# CPU.net
KiCad netlist of a schematic drawn in Altium Designer
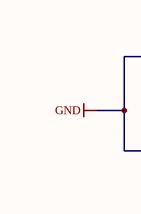
[diagram p0: CPU.SchDoc, top left]
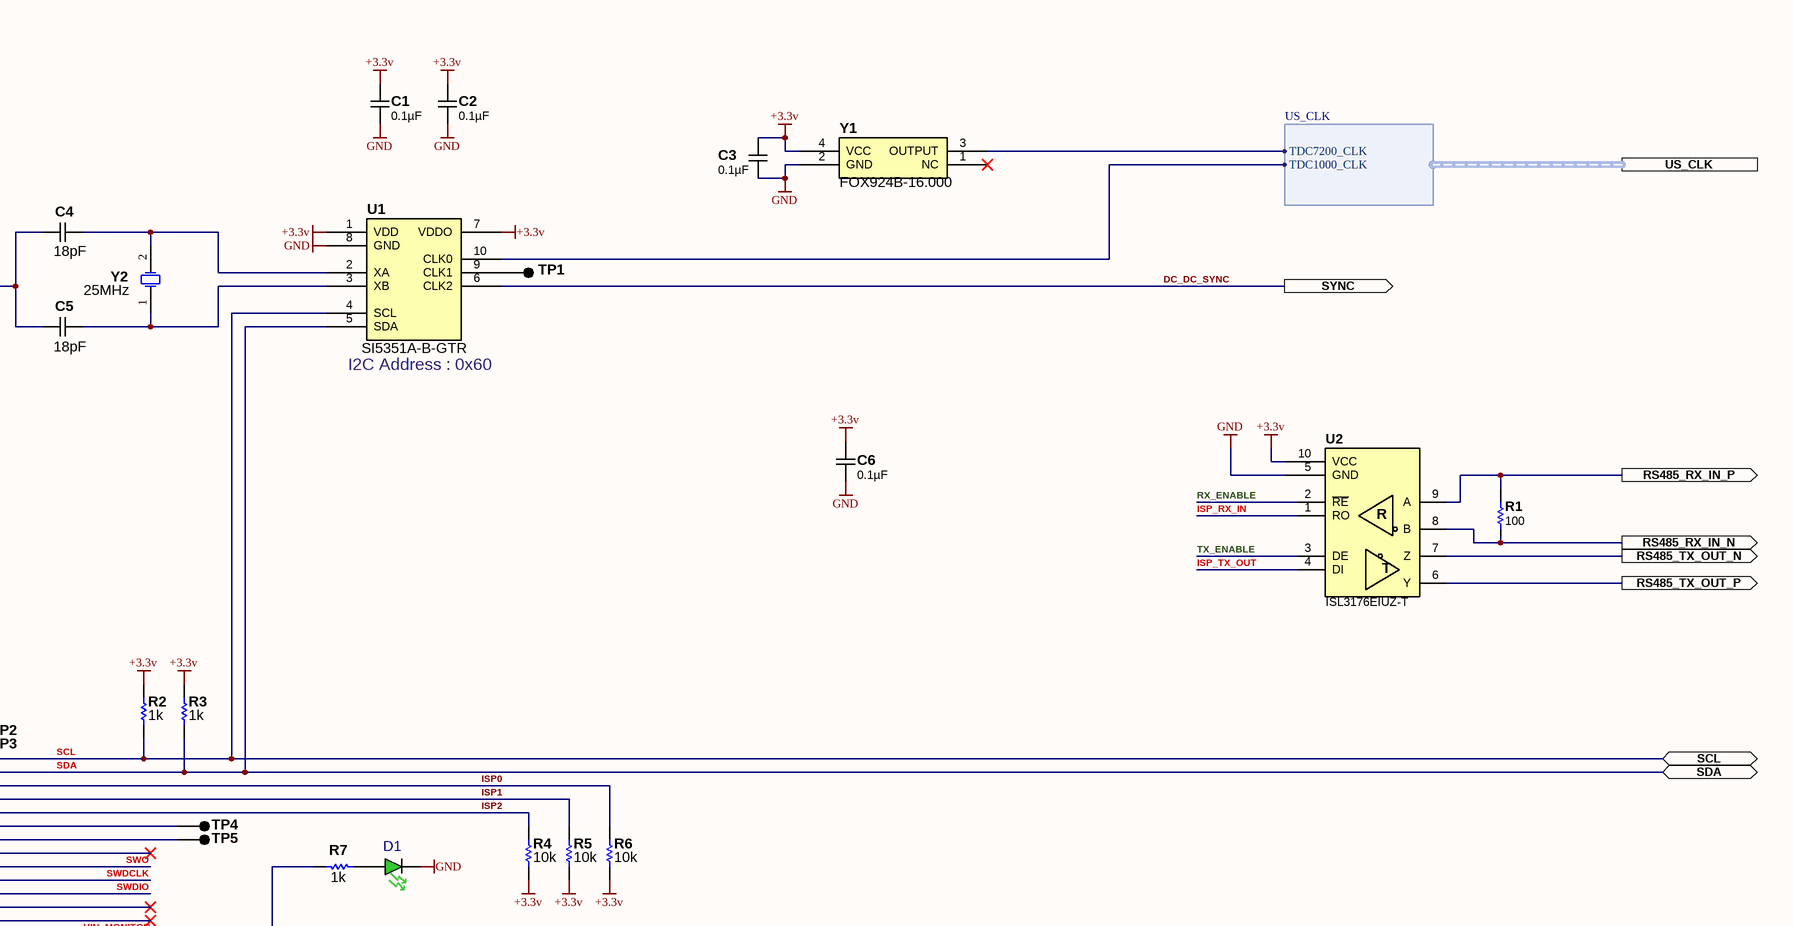
[diagram p1: CPU.SchDoc, top right]
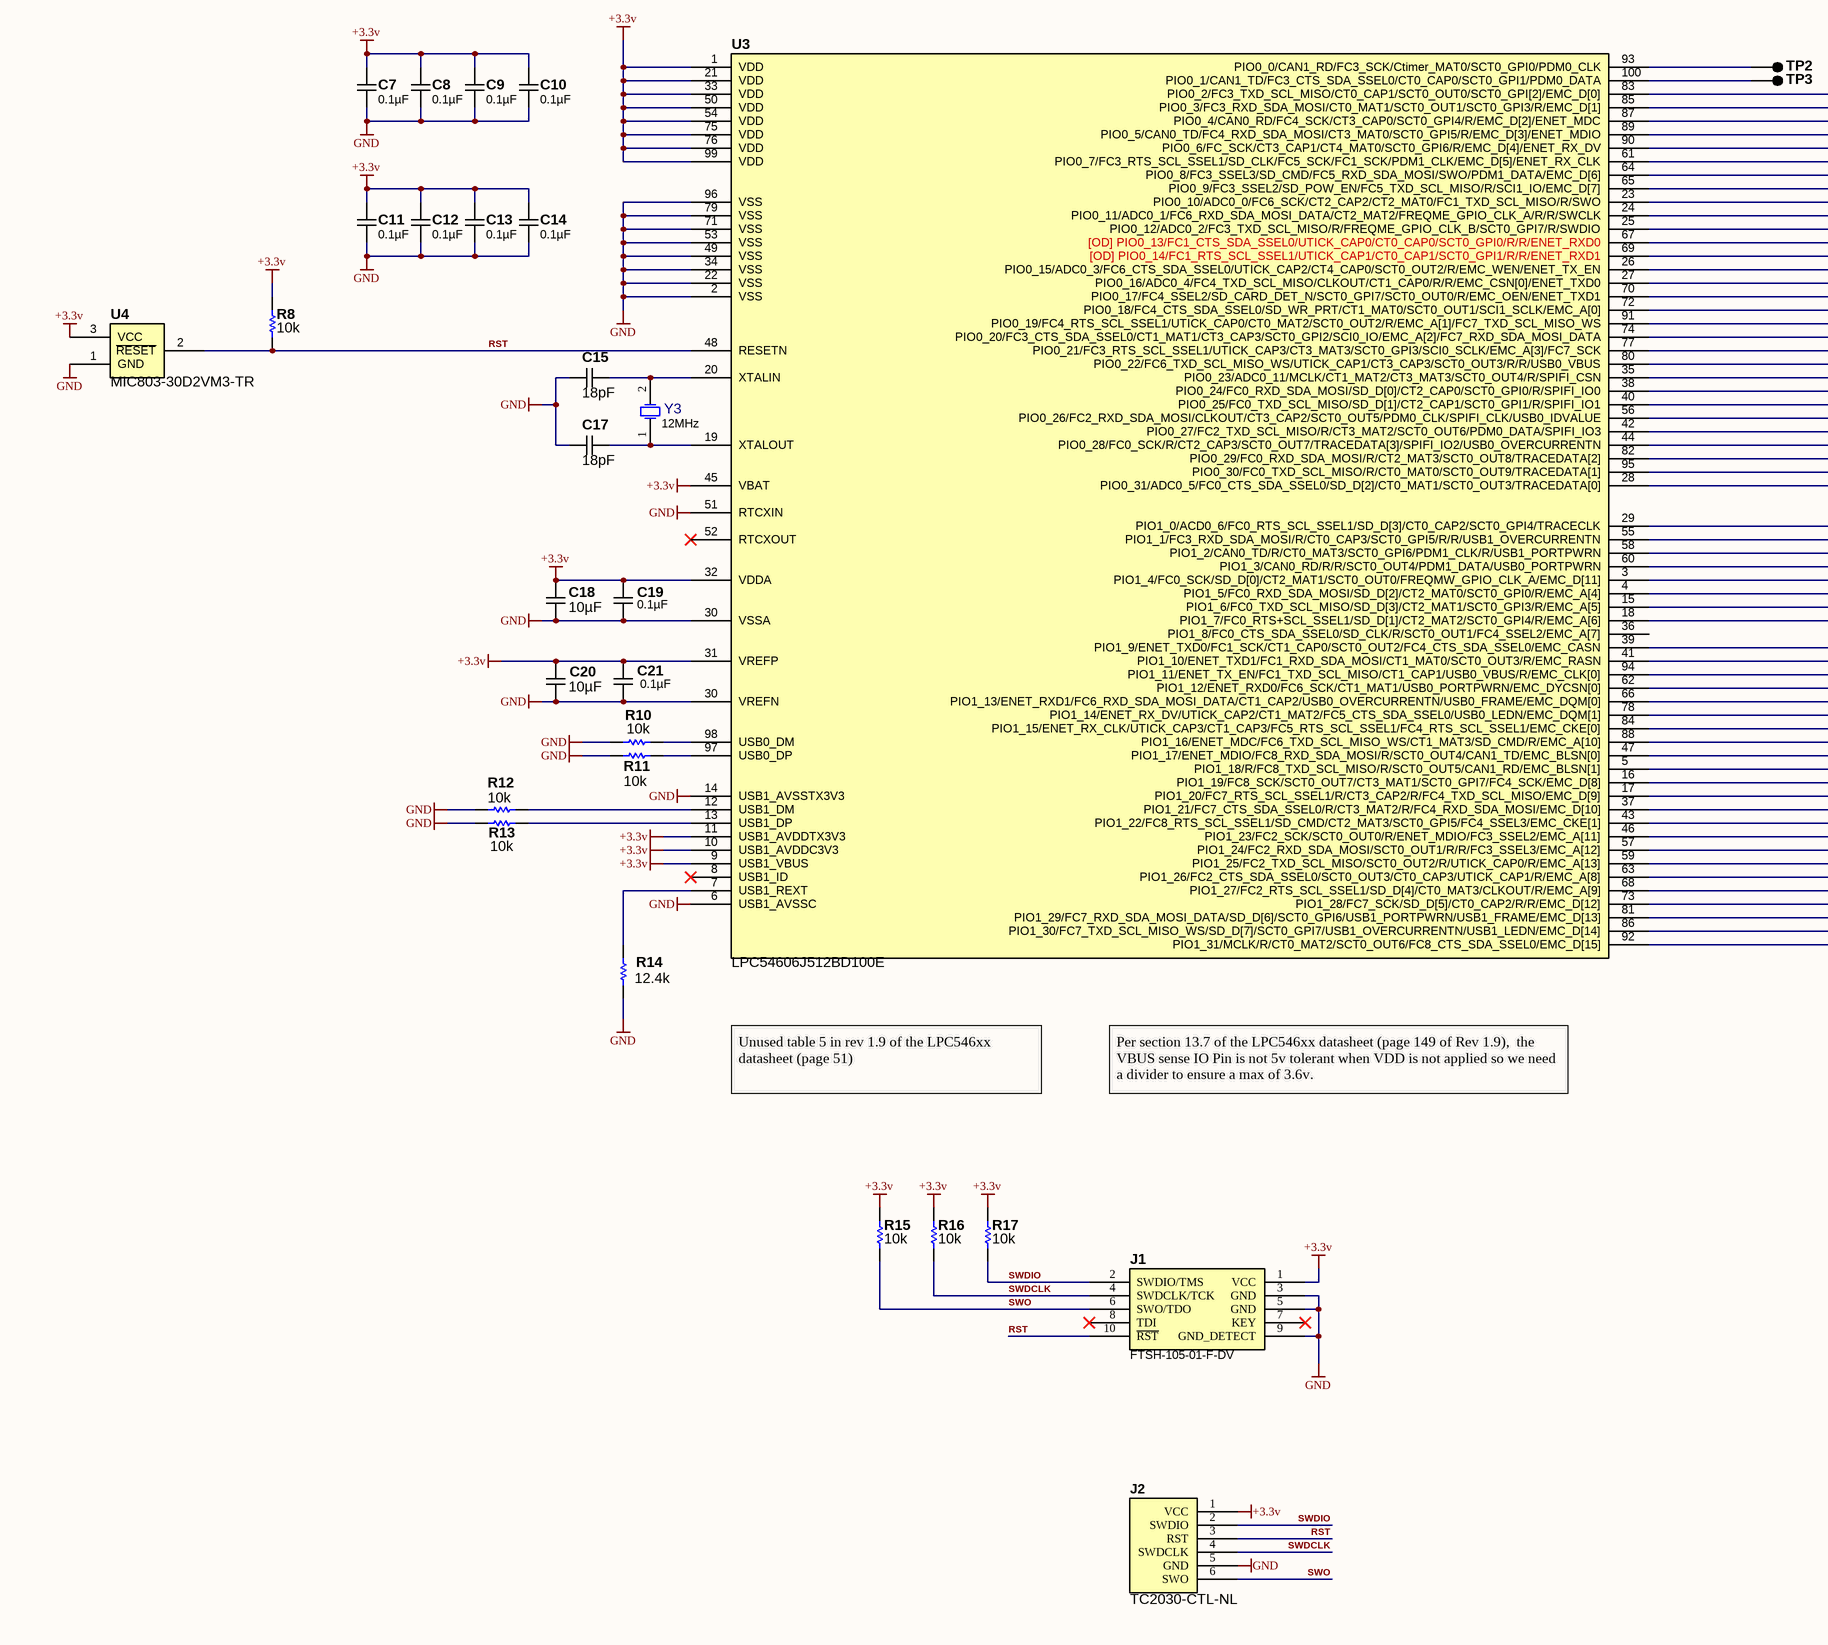
[diagram p2: CPU.SchDoc, bottom left]
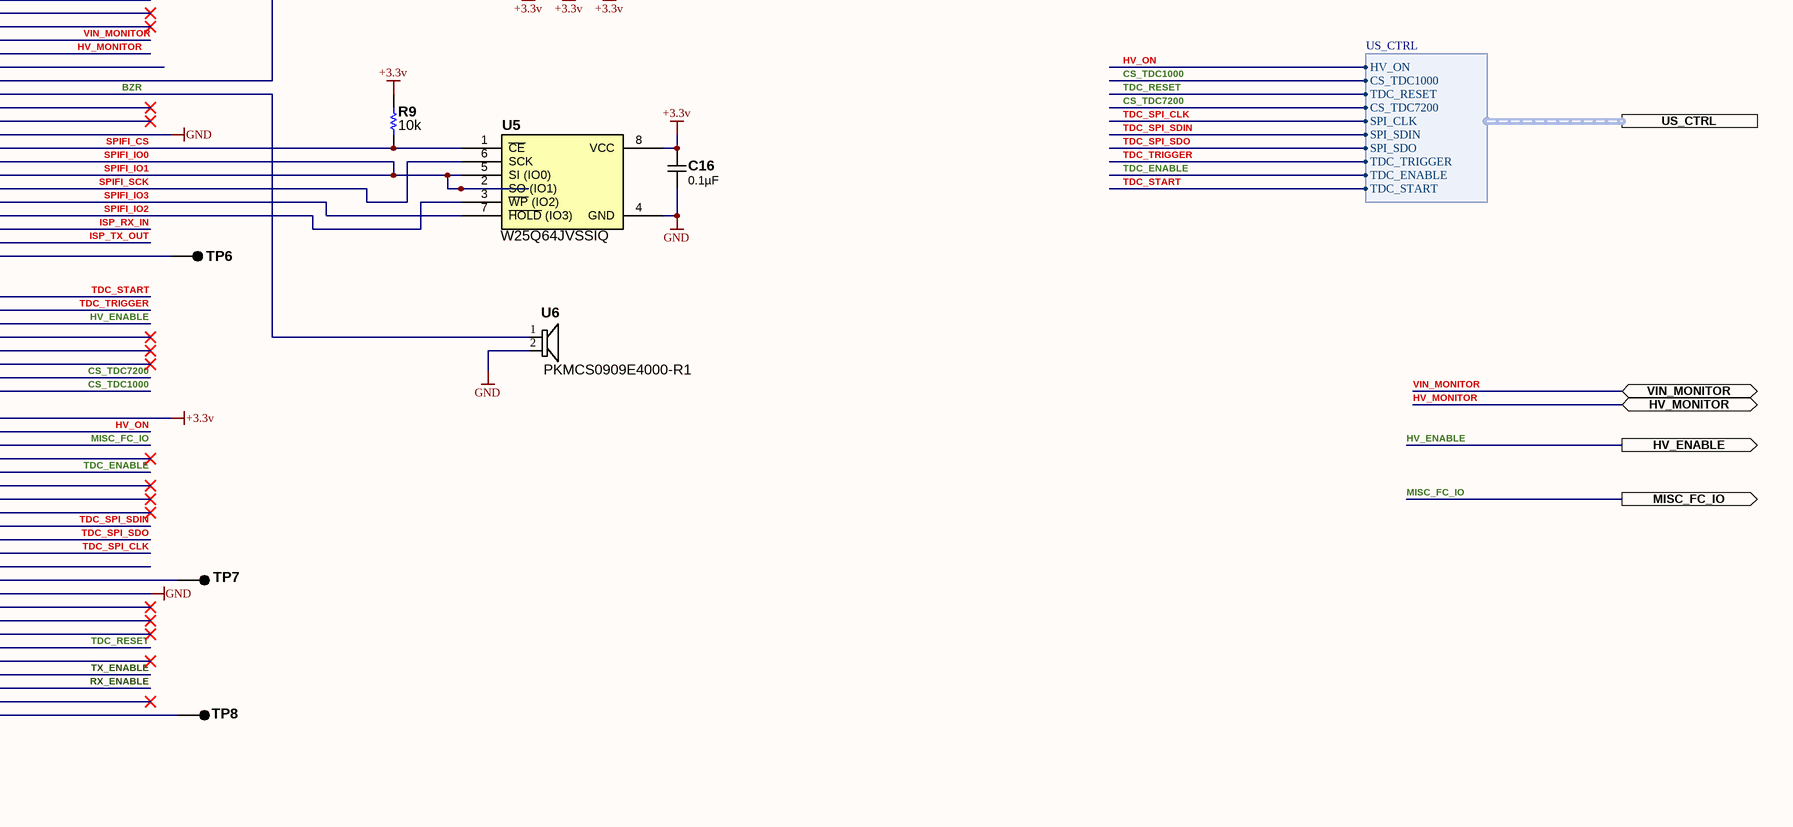
[diagram p3: CPU.SchDoc, bottom right]

(export (version "E")
  (design (tool "Eeschema 10.0.6"))
  (components
    (comp (ref "C1")
      (value "0.1µF")
      (footprint "C0603_0.90MM_HD")
      (description "CAP CER 0.1UF 50V X7R 0603")
      (fields
        (field (name "MANUFACTURER PART NUMBER") "CGA3E2X7R1H104K080AE")
        (field (name "MANUFACTURER") "TDK Corporation")
      )
      (libsource (lib "Capacitors - TDK- AEC-Q200") (part "C_2P_NP"))
    )
    (comp (ref "C2")
      (value "0.1µF")
      (footprint "C0603_0.90MM_HD")
      (description "CAP CER 0.1UF 50V X7R 0603")
      (fields
        (field (name "MANUFACTURER PART NUMBER") "CGA3E2X7R1H104K080AE")
        (field (name "MANUFACTURER") "TDK Corporation")
      )
      (libsource (lib "Capacitors - TDK- AEC-Q200") (part "C_2P_NP"))
    )
    (comp (ref "C3")
      (value "0.1µF")
      (footprint "C0603_0.90MM_HD")
      (description "CAP CER 0.1UF 50V X7R 0603")
      (fields
        (field (name "MANUFACTURER PART NUMBER") "CGA3E2X7R1H104K080AE")
        (field (name "MANUFACTURER") "TDK Corporation")
      )
      (libsource (lib "Capacitors - TDK- AEC-Q200") (part "C_2P_NP"))
    )
    (comp (ref "C4")
      (value "18pF")
      (footprint "C0603_0.90MM_HD")
      (description "CAP CER 18PF 50V C0G 0603")
      (fields
        (field (name "MANUFACTURER PART NUMBER") "CGA3E2C0G1H180J080AA")
        (field (name "MANUFACTURER") "TDK Corporation")
      )
      (libsource (lib "Capacitors - TDK- AEC-Q200") (part "C_2P_NP"))
    )
    (comp (ref "C5")
      (value "18pF")
      (footprint "C0603_0.90MM_HD")
      (description "CAP CER 18PF 50V C0G 0603")
      (fields
        (field (name "MANUFACTURER PART NUMBER") "CGA3E2C0G1H180J080AA")
        (field (name "MANUFACTURER") "TDK Corporation")
      )
      (libsource (lib "Capacitors - TDK- AEC-Q200") (part "C_2P_NP"))
    )
    (comp (ref "C6")
      (value "0.1µF")
      (footprint "C0603_0.90MM_HD")
      (description "CAP CER 0.1UF 50V X7R 0603")
      (fields
        (field (name "MANUFACTURER PART NUMBER") "CGA3E2X7R1H104K080AE")
        (field (name "MANUFACTURER") "TDK Corporation")
      )
      (libsource (lib "Capacitors - TDK- AEC-Q200") (part "C_2P_NP"))
    )
    (comp (ref "C7")
      (value "0.1µF")
      (footprint "C0603_0.90MM_HD")
      (description "CAP CER 0.1UF 50V X7R 0603")
      (fields
        (field (name "MANUFACTURER PART NUMBER") "CGA3E2X7R1H104K080AE")
        (field (name "MANUFACTURER") "TDK Corporation")
      )
      (libsource (lib "Capacitors - TDK- AEC-Q200") (part "C_2P_NP"))
    )
    (comp (ref "C8")
      (value "0.1µF")
      (footprint "C0603_0.90MM_HD")
      (description "CAP CER 0.1UF 50V X7R 0603")
      (fields
        (field (name "MANUFACTURER PART NUMBER") "CGA3E2X7R1H104K080AE")
        (field (name "MANUFACTURER") "TDK Corporation")
      )
      (libsource (lib "Capacitors - TDK- AEC-Q200") (part "C_2P_NP"))
    )
    (comp (ref "C9")
      (value "0.1µF")
      (footprint "C0603_0.90MM_HD")
      (description "CAP CER 0.1UF 50V X7R 0603")
      (fields
        (field (name "MANUFACTURER PART NUMBER") "CGA3E2X7R1H104K080AE")
        (field (name "MANUFACTURER") "TDK Corporation")
      )
      (libsource (lib "Capacitors - TDK- AEC-Q200") (part "C_2P_NP"))
    )
    (comp (ref "C10")
      (value "0.1µF")
      (footprint "C0603_0.90MM_HD")
      (description "CAP CER 0.1UF 50V X7R 0603")
      (fields
        (field (name "MANUFACTURER PART NUMBER") "CGA3E2X7R1H104K080AE")
        (field (name "MANUFACTURER") "TDK Corporation")
      )
      (libsource (lib "Capacitors - TDK- AEC-Q200") (part "C_2P_NP"))
    )
    (comp (ref "C11")
      (value "0.1µF")
      (footprint "C0603_0.90MM_HD")
      (description "CAP CER 0.1UF 50V X7R 0603")
      (fields
        (field (name "MANUFACTURER PART NUMBER") "CGA3E2X7R1H104K080AE")
        (field (name "MANUFACTURER") "TDK Corporation")
      )
      (libsource (lib "Capacitors - TDK- AEC-Q200") (part "C_2P_NP"))
    )
    (comp (ref "C12")
      (value "0.1µF")
      (footprint "C0603_0.90MM_HD")
      (description "CAP CER 0.1UF 50V X7R 0603")
      (fields
        (field (name "MANUFACTURER PART NUMBER") "CGA3E2X7R1H104K080AE")
        (field (name "MANUFACTURER") "TDK Corporation")
      )
      (libsource (lib "Capacitors - TDK- AEC-Q200") (part "C_2P_NP"))
    )
    (comp (ref "C13")
      (value "0.1µF")
      (footprint "C0603_0.90MM_HD")
      (description "CAP CER 0.1UF 50V X7R 0603")
      (fields
        (field (name "MANUFACTURER PART NUMBER") "CGA3E2X7R1H104K080AE")
        (field (name "MANUFACTURER") "TDK Corporation")
      )
      (libsource (lib "Capacitors - TDK- AEC-Q200") (part "C_2P_NP"))
    )
    (comp (ref "C14")
      (value "0.1µF")
      (footprint "C0603_0.90MM_HD")
      (description "CAP CER 0.1UF 50V X7R 0603")
      (fields
        (field (name "MANUFACTURER PART NUMBER") "CGA3E2X7R1H104K080AE")
        (field (name "MANUFACTURER") "TDK Corporation")
      )
      (libsource (lib "Capacitors - TDK- AEC-Q200") (part "C_2P_NP"))
    )
    (comp (ref "C15")
      (value "18pF")
      (footprint "C0603_0.90MM_HD")
      (description "CAP CER 18PF 50V C0G 0603")
      (fields
        (field (name "MANUFACTURER PART NUMBER") "CGA3E2C0G1H180J080AA")
        (field (name "MANUFACTURER") "TDK Corporation")
      )
      (libsource (lib "Capacitors - TDK- AEC-Q200") (part "C_2P_NP"))
    )
    (comp (ref "C16")
      (value "0.1µF")
      (footprint "C0603_0.90MM_HD")
      (description "CAP CER 0.1UF 50V X7R 0603")
      (fields
        (field (name "MANUFACTURER PART NUMBER") "CGA3E2X7R1H104K080AE")
        (field (name "MANUFACTURER") "TDK Corporation")
      )
      (libsource (lib "Capacitors - TDK- AEC-Q200") (part "C_2P_NP"))
    )
    (comp (ref "C17")
      (value "18pF")
      (footprint "C0603_0.90MM_HD")
      (description "CAP CER 18PF 50V C0G 0603")
      (fields
        (field (name "MANUFACTURER PART NUMBER") "CGA3E2C0G1H180J080AA")
        (field (name "MANUFACTURER") "TDK Corporation")
      )
      (libsource (lib "Capacitors - TDK- AEC-Q200") (part "C_2P_NP"))
    )
    (comp (ref "C18")
      (value "10µF")
      (footprint "C0805_1.45MM_HD")
      (description "CAP CER 10UF 6.3V X7R 0805")
      (fields
        (field (name "MANUFACTURER PART NUMBER") "CGA4J1X7R0J106K125AC")
        (field (name "MANUFACTURER") "TDK Corporation")
      )
      (libsource (lib "Capacitors - TDK- AEC-Q200") (part "C_2P_NP"))
    )
    (comp (ref "C19")
      (value "0.1µF")
      (footprint "C0603_0.90MM_HD")
      (description "CAP CER 0.1UF 50V X7R 0603")
      (fields
        (field (name "MANUFACTURER PART NUMBER") "CGA3E2X7R1H104K080AE")
        (field (name "MANUFACTURER") "TDK Corporation")
      )
      (libsource (lib "Capacitors - TDK- AEC-Q200") (part "C_2P_NP"))
    )
    (comp (ref "C20")
      (value "10µF")
      (footprint "C0805_1.45MM_HD")
      (description "CAP CER 10UF 6.3V X7R 0805")
      (fields
        (field (name "MANUFACTURER PART NUMBER") "CGA4J1X7R0J106K125AC")
        (field (name "MANUFACTURER") "TDK Corporation")
      )
      (libsource (lib "Capacitors - TDK- AEC-Q200") (part "C_2P_NP"))
    )
    (comp (ref "C21")
      (value "0.1µF")
      (footprint "C0603_0.90MM_HD")
      (description "CAP CER 0.1UF 50V X7R 0603")
      (fields
        (field (name "MANUFACTURER PART NUMBER") "CGA3E2X7R1H104K080AE")
        (field (name "MANUFACTURER") "TDK Corporation")
      )
      (libsource (lib "Capacitors - TDK- AEC-Q200") (part "C_2P_NP"))
    )
    (comp (ref "D1")
      (value "LED 1.6X0.8MM 570NM GRN CLR SMD")
      (footprint "LED_0603 - GREEN")
      (fields
        (field (name "MANUFACTURER") "Kingbright Corp")
        (field (name "MANUFACTURER PART NUMBER") "APT1608CGCK")
      )
      (libsource (lib "eDiode") (part "APT1608CGCK"))
    )
    (comp (ref "J1")
      (value "FTSH-105-01-F-DV")
      (footprint "FTSH-105-04-F-DV - HD")
      (description "SAMTEC - FTSH-105-01-F-DV - .050 X .050")
      (fields (field (name "MANUFACTURER") "SAMTEC"))
      (libsource (lib "eConnector") (part "CORTEX-DEBUG"))
    )
    (comp (ref "J2")
      (value "TC2030‐CTL‐NL")
      (footprint "TC2030 NO LATCH")
      (description "Tag Connect Pads - No latching Clips - ARM")
      (libsource (lib "eConnector") (part "TC2030‐CTL‐NL"))
    )
    (comp (ref "R1")
      (value "100")
      (footprint "R0603_HD")
      (description "RES 100 OHM 1/10W 1% 0603 SMD")
      (fields
        (field (name "MANUFACTURER PART NUMBER") "ERJ-3EKF1000V")
        (field (name "MANUFACTURER") "Panasonic Electronic Components")
      )
      (libsource (lib "Resistors - Panasonic - AEC-Q200") (part "R_2P"))
    )
    (comp (ref "R2")
      (value "1k")
      (footprint "R0603_0.55MM_HD")
      (description "RES 1K OHM 1/10W 1% 0603 SMD")
      (fields
        (field (name "MANUFACTURER PART NUMBER") "ERJ-3EKF1001V")
        (field (name "MANUFACTURER") "Panasonic Electronic Components")
      )
      (libsource (lib "Resistors - Panasonic - AEC-Q200") (part "R_2P"))
    )
    (comp (ref "R3")
      (value "1k")
      (footprint "R0603_0.55MM_HD")
      (description "RES 1K OHM 1/10W 1% 0603 SMD")
      (fields
        (field (name "MANUFACTURER PART NUMBER") "ERJ-3EKF1001V")
        (field (name "MANUFACTURER") "Panasonic Electronic Components")
      )
      (libsource (lib "Resistors - Panasonic - AEC-Q200") (part "R_2P"))
    )
    (comp (ref "R4")
      (value "10k")
      (footprint "R0603_0.55MM_HD")
      (description "RES 10K OHM 1/10W 1% 0603 SMD")
      (fields
        (field (name "MANUFACTURER PART NUMBER") "ERJ-3EKF1002V")
        (field (name "MANUFACTURER") "Panasonic Electronic Components")
      )
      (libsource (lib "Resistors - Panasonic - AEC-Q200") (part "R_2P"))
    )
    (comp (ref "R5")
      (value "10k")
      (footprint "R0603_0.55MM_HD")
      (description "RES 10K OHM 1/10W 1% 0603 SMD")
      (fields
        (field (name "MANUFACTURER PART NUMBER") "ERJ-3EKF1002V")
        (field (name "MANUFACTURER") "Panasonic Electronic Components")
      )
      (libsource (lib "Resistors - Panasonic - AEC-Q200") (part "R_2P"))
    )
    (comp (ref "R6")
      (value "10k")
      (footprint "R0603_0.55MM_HD")
      (description "RES 10K OHM 1/10W 1% 0603 SMD")
      (fields
        (field (name "MANUFACTURER PART NUMBER") "ERJ-3EKF1002V")
        (field (name "MANUFACTURER") "Panasonic Electronic Components")
      )
      (libsource (lib "Resistors - Panasonic - AEC-Q200") (part "R_2P"))
    )
    (comp (ref "R7")
      (value "1k")
      (footprint "R0603_0.55MM_HD")
      (description "RES 1K OHM 1/10W 1% 0603 SMD")
      (fields
        (field (name "MANUFACTURER PART NUMBER") "ERJ-3EKF1001V")
        (field (name "MANUFACTURER") "Panasonic Electronic Components")
      )
      (libsource (lib "Resistors - Panasonic - AEC-Q200") (part "R_2P"))
    )
    (comp (ref "R8")
      (value "10k")
      (footprint "R0603_0.55MM_HD")
      (description "RES 10K OHM 1/10W 1% 0603 SMD")
      (fields
        (field (name "MANUFACTURER PART NUMBER") "ERJ-3EKF1002V")
        (field (name "MANUFACTURER") "Panasonic Electronic Components")
      )
      (libsource (lib "Resistors - Panasonic - AEC-Q200") (part "R_2P"))
    )
    (comp (ref "R9")
      (value "10k")
      (footprint "R0603_0.55MM_HD")
      (description "RES 10K OHM 1/10W 1% 0603 SMD")
      (fields
        (field (name "MANUFACTURER PART NUMBER") "ERJ-3EKF1002V")
        (field (name "MANUFACTURER") "Panasonic Electronic Components")
      )
      (libsource (lib "Resistors - Panasonic - AEC-Q200") (part "R_2P"))
    )
    (comp (ref "R10")
      (value "10k")
      (footprint "R0603_0.55MM_HD")
      (description "RES 10K OHM 1/10W 1% 0603 SMD")
      (fields
        (field (name "MANUFACTURER PART NUMBER") "ERJ-3EKF1002V")
        (field (name "MANUFACTURER") "Panasonic Electronic Components")
      )
      (libsource (lib "Resistors - Panasonic - AEC-Q200") (part "R_2P"))
    )
    (comp (ref "R11")
      (value "10k")
      (footprint "R0603_0.55MM_HD")
      (description "RES 10K OHM 1/10W 1% 0603 SMD")
      (fields
        (field (name "MANUFACTURER PART NUMBER") "ERJ-3EKF1002V")
        (field (name "MANUFACTURER") "Panasonic Electronic Components")
      )
      (libsource (lib "Resistors - Panasonic - AEC-Q200") (part "R_2P"))
    )
    (comp (ref "R12")
      (value "10k")
      (footprint "R0603_0.55MM_HD")
      (description "RES 10K OHM 1/10W 1% 0603 SMD")
      (fields
        (field (name "MANUFACTURER PART NUMBER") "ERJ-3EKF1002V")
        (field (name "MANUFACTURER") "Panasonic Electronic Components")
      )
      (libsource (lib "Resistors - Panasonic - AEC-Q200") (part "R_2P"))
    )
    (comp (ref "R13")
      (value "10k")
      (footprint "R0603_0.55MM_HD")
      (description "RES 10K OHM 1/10W 1% 0603 SMD")
      (fields
        (field (name "MANUFACTURER PART NUMBER") "ERJ-3EKF1002V")
        (field (name "MANUFACTURER") "Panasonic Electronic Components")
      )
      (libsource (lib "Resistors - Panasonic - AEC-Q200") (part "R_2P"))
    )
    (comp (ref "R14")
      (value "12.4k")
      (footprint "R0603_0.55MM_HD")
      (description "RES 12.4K OHM 1/10W 1% 0603 SMD")
      (fields
        (field (name "MANUFACTURER PART NUMBER") "ERJ-3EKF1242V")
        (field (name "MANUFACTURER") "Panasonic Electronic Components")
      )
      (libsource (lib "Resistors - Panasonic - AEC-Q200") (part "R_2P"))
    )
    (comp (ref "R15")
      (value "10k")
      (footprint "R0603_0.55MM_HD")
      (description "RES 10K OHM 1/10W 1% 0603 SMD")
      (fields
        (field (name "MANUFACTURER PART NUMBER") "ERJ-3EKF1002V")
        (field (name "MANUFACTURER") "Panasonic Electronic Components")
      )
      (libsource (lib "Resistors - Panasonic - AEC-Q200") (part "R_2P"))
    )
    (comp (ref "R16")
      (value "10k")
      (footprint "R0603_0.55MM_HD")
      (description "RES 10K OHM 1/10W 1% 0603 SMD")
      (fields
        (field (name "MANUFACTURER PART NUMBER") "ERJ-3EKF1002V")
        (field (name "MANUFACTURER") "Panasonic Electronic Components")
      )
      (libsource (lib "Resistors - Panasonic - AEC-Q200") (part "R_2P"))
    )
    (comp (ref "R17")
      (value "10k")
      (footprint "R0603_0.55MM_HD")
      (description "RES 10K OHM 1/10W 1% 0603 SMD")
      (fields
        (field (name "MANUFACTURER PART NUMBER") "ERJ-3EKF1002V")
        (field (name "MANUFACTURER") "Panasonic Electronic Components")
      )
      (libsource (lib "Resistors - Panasonic - AEC-Q200") (part "R_2P"))
    )
    (comp (ref "TP1")
      (value "SMT_TEST")
      (footprint "SMT_TP - 25")
      (libsource (lib "Hydroscope") (part "SMT_TEST"))
    )
    (comp (ref "TP2")
      (value "SMT_TEST")
      (footprint "SMT_TP - 25")
      (libsource (lib "Hydroscope") (part "SMT_TEST"))
    )
    (comp (ref "TP3")
      (value "SMT_TEST")
      (footprint "SMT_TP - 25")
      (libsource (lib "Hydroscope") (part "SMT_TEST"))
    )
    (comp (ref "TP4")
      (value "SMT_TEST")
      (footprint "SMT_TP - 25")
      (libsource (lib "Hydroscope") (part "SMT_TEST"))
    )
    (comp (ref "TP5")
      (value "SMT_TEST")
      (footprint "SMT_TP - 25")
      (libsource (lib "Hydroscope") (part "SMT_TEST"))
    )
    (comp (ref "TP6")
      (value "SMT_TEST")
      (footprint "SMT_TP - 25")
      (libsource (lib "Hydroscope") (part "SMT_TEST"))
    )
    (comp (ref "TP7")
      (value "SMT_TEST")
      (footprint "SMT_TP - 25")
      (libsource (lib "Hydroscope") (part "SMT_TEST"))
    )
    (comp (ref "TP8")
      (value "SMT_TEST")
      (footprint "SMT_TP - 25")
      (libsource (lib "Hydroscope") (part "SMT_TEST"))
    )
    (comp (ref "U1")
      (value "SI5351A-B-GTR")
      (footprint "10 MSOP")
      (description "Clock Generators & Support Products Any-Rate, Dual PLL 1 60MHz Clock 8outputs")
      (fields (field (name "MANUFACTURER") "Silicon Labs"))
      (libsource (lib "eIC") (part "SI5351A-B-GTR"))
    )
    (comp (ref "U2")
      (value "ISL3176EIUZ-T")
      (footprint "10 MSOP")
      (description "IC TXRX RS422/485 20MBPS 10MSOP")
      (fields (field (name "MANUFACTURER") "Intersil"))
      (libsource (lib "eIC") (part "ISL3176EIUZ-T"))
    )
    (comp (ref "U3")
      (value "LPC54606J512BD100E")
      (footprint "TSQFP50P1600X1600X160-100N")
      (description "32-BIT ARM CORTEX-M4")
      (fields (field (name "MANUFACTURER") "NXP USA Inc."))
      (libsource (lib "eIC") (part "LPC54606J512BD100E"))
    )
    (comp (ref "U4")
      (value "MIC803-30D2VM3-TR")
      (footprint "SOT-23")
      (description "3-Pin Microprocessor Supervisor Circuit w/ Open-Drain Reset Output, 3 SOT-23 - T/R")
      (fields (field (name "MANUFACTURER") "Microchip"))
      (libsource (lib "eIC") (part "MIC803-30D2VM3-TR"))
    )
    (comp (ref "U5")
      (value "W25Q64JVSSIQ")
      (footprint "SOIC127P830X200-8L")
      (description "NOR Flash Serial-SPI 3V 64MBit 64M x 1bit 6ns 8-Pin SOIC")
      (fields (field (name "MANUFACTURER") "Winbond"))
      (libsource (lib "eIC") (part "W25Q64JVSSIQ"))
    )
    (comp (ref "U6")
      (value "PKMCS0909E4000-R1")
      (footprint "PKMCS0909E4000-R1")
      (description "Audio Indicators & Alerts Piezo Buzzer 9x9mm 4KHz 1.9mm Thickness")
      (fields (field (name "MANUFACTURER") "Murata"))
      (libsource (lib "eAudio") (part "PKMCS0909E4000-R1"))
    )
    (comp (ref "Y1")
      (value "FOX924B-16.000")
      (footprint "FOX924")
      (description "OSC TCXO 16.000MHZ HCMOS SMD")
      (fields (field (name "MANUFACTURER") "Fox Electronics"))
      (libsource (lib "eCrystal") (part "FOX924B-16.000"))
    )
    (comp (ref "Y2")
      (value "25MHz")
      (footprint "ABM3")
      (description "25MHz ±30ppm Crystal 18pF 30 Ohm -20°C ~ 70°C  Surface Mount 2-SMD, No Lead (DFN, LCC)")
      (fields
        (field (name "MANUFACTURER") "Abracon")
        (field (name "MANUFACTURER PART NUMBER") "ABM3-25.000MHZ-B4Y-T")
      )
      (libsource (lib "eCrystal") (part "ABM3-25.000MHZ-B4Y-T"))
    )
    (comp (ref "Y3")
      (value "12MHz")
      (footprint "ABM3")
      (description "CRYSTAL 12.000MHZ 18PF SMD")
      (fields
        (field (name "MANUFACTURER") "Abracon Corporation")
        (field (name "MANUFACTURER PART NUMBER") "ABM3-12.000MHZ-B2-T")
      )
      (libsource (lib "eCrystal") (part "ABM3-12.000MHZ-B2-T"))
    )
  )
  (nets
    (net (code "3") (name "+3.3v") (class "Default")
      (node (ref "C1") (pin "2") (pinfunction "1_2") (pintype "passive"))
      (node (ref "C10") (pin "2") (pinfunction "1_2") (pintype "passive"))
      (node (ref "C11") (pin "2") (pinfunction "1_2") (pintype "passive"))
      (node (ref "C12") (pin "2") (pinfunction "1_2") (pintype "passive"))
      (node (ref "C13") (pin "2") (pinfunction "1_2") (pintype "passive"))
      (node (ref "C14") (pin "2") (pinfunction "1_2") (pintype "passive"))
      (node (ref "C16") (pin "2") (pinfunction "1_2") (pintype "passive"))
      (node (ref "C18") (pin "2") (pinfunction "1_2") (pintype "passive"))
      (node (ref "C19") (pin "2") (pinfunction "1_2") (pintype "passive"))
      (node (ref "C2") (pin "2") (pinfunction "1_2") (pintype "passive"))
      (node (ref "C20") (pin "2") (pinfunction "1_2") (pintype "passive"))
      (node (ref "C21") (pin "2") (pinfunction "1_2") (pintype "passive"))
      (node (ref "C3") (pin "2") (pinfunction "1_2") (pintype "passive"))
      (node (ref "C6") (pin "1") (pinfunction "1_1") (pintype "passive"))
      (node (ref "C7") (pin "2") (pinfunction "1_2") (pintype "passive"))
      (node (ref "C8") (pin "2") (pinfunction "1_2") (pintype "passive"))
      (node (ref "C9") (pin "2") (pinfunction "1_2") (pintype "passive"))
      (node (ref "J1") (pin "1") (pinfunction "VCC_1") (pintype "passive"))
      (node (ref "J2") (pin "1") (pinfunction "VCC_1") (pintype "passive"))
      (node (ref "R15") (pin "2") (pinfunction "2_2") (pintype "passive"))
      (node (ref "R16") (pin "2") (pinfunction "2_2") (pintype "passive"))
      (node (ref "R17") (pin "2") (pinfunction "2_2") (pintype "passive"))
      (node (ref "R2") (pin "2") (pinfunction "2_2") (pintype "passive"))
      (node (ref "R3") (pin "2") (pinfunction "2_2") (pintype "passive"))
      (node (ref "R4") (pin "1") (pinfunction "1_1") (pintype "passive"))
      (node (ref "R5") (pin "1") (pinfunction "1_1") (pintype "passive"))
      (node (ref "R6") (pin "1") (pinfunction "1_1") (pintype "passive"))
      (node (ref "R8") (pin "2") (pinfunction "2_2") (pintype "passive"))
      (node (ref "R9") (pin "2") (pinfunction "2_2") (pintype "passive"))
      (node (ref "U1") (pin "1") (pinfunction "VDD_1") (pintype "passive"))
      (node (ref "U1") (pin "7") (pinfunction "VDDO_7") (pintype "passive"))
      (node (ref "U2") (pin "10") (pinfunction "VCC_10") (pintype "passive"))
      (node (ref "U3") (pin "1") (pinfunction "VDD_1") (pintype "passive"))
      (node (ref "U3") (pin "10") (pinfunction "USB1_AVDDC3V3_10") (pintype "passive"))
      (node (ref "U3") (pin "11") (pinfunction "USB1_AVDDTX3V3_11") (pintype "passive"))
      (node (ref "U3") (pin "21") (pinfunction "VDD_21") (pintype "passive"))
      (node (ref "U3") (pin "31") (pinfunction "VREFP_31") (pintype "passive"))
      (node (ref "U3") (pin "32") (pinfunction "VDDA_32") (pintype "passive"))
      (node (ref "U3") (pin "33") (pinfunction "VDD_33") (pintype "passive"))
      (node (ref "U3") (pin "39") (pinfunction "PIO1_9/ENET_TXD0/FC1_SCK/CT1_CAP0/SCT0_OUT2/FC4_CTS_SDA_SSEL0/EMC_CASN_39") (pintype "passive"))
      (node (ref "U3") (pin "45") (pinfunction "VBAT_45") (pintype "passive"))
      (node (ref "U3") (pin "50") (pinfunction "VDD_50") (pintype "passive"))
      (node (ref "U3") (pin "54") (pinfunction "VDD_54") (pintype "passive"))
      (node (ref "U3") (pin "75") (pinfunction "VDD_75") (pintype "passive"))
      (node (ref "U3") (pin "76") (pinfunction "VDD_76") (pintype "passive"))
      (node (ref "U3") (pin "9") (pinfunction "USB1_VBUS_9") (pintype "passive"))
      (node (ref "U3") (pin "99") (pinfunction "VDD_99") (pintype "passive"))
      (node (ref "U4") (pin "3") (pinfunction "VCC_3") (pintype "passive"))
      (node (ref "U5") (pin "8") (pinfunction "VCC_8") (pintype "passive"))
      (node (ref "Y1") (pin "4") (pinfunction "VCC_4") (pintype "passive"))
    )
    (net (code "4") (name "/BZR") (class "Default")
      (node (ref "U3") (pin "91") (pinfunction "PIO0_19/FC4_RTS_SCL_SSEL1/UTICK_CAP0/CT0_MAT2/SCT0_OUT2/R/EMC_A[1]/FC7_TXD_SCL_MISO_WS_91") (pintype "passive"))
      (node (ref "U6") (pin "1") (pinfunction "+_1") (pintype "passive"))
    )
    (net (code "5") (name "/CS_TDC1000") (class "Default")
      (node (ref "U3") (pin "18") (pinfunction "PIO1_7/FC0_RTS+SCL_SSEL1/SD_D[1]/CT2_MAT2/SCT0_GPI4/R/EMC_A[6]_18") (pintype "passive"))
    )
    (net (code "6") (name "/CS_TDC7200") (class "Default")
      (node (ref "U3") (pin "15") (pinfunction "PIO1_6/FC0_TXD_SCL_MISO/SD_D[3]/CT2_MAT1/SCT0_GPI3/R/EMC_A[5]_15") (pintype "passive"))
    )
    (net (code "7") (name "/DC_DC_SYNC") (class "Default")
      (node (ref "U1") (pin "6") (pinfunction "CLK2_6") (pintype "passive"))
    )
    (net (code "8") (name "/HV_ENABLE") (class "Default")
      (node (ref "U3") (pin "58") (pinfunction "PIO1_2/CAN0_TD/R/CT0_MAT3/SCT0_GPI6/PDM1_CLK/R/USB1_PORTPWRN_58") (pintype "passive"))
    )
    (net (code "9") (name "/HV_MONITOR") (class "Default")
      (node (ref "U3") (pin "27") (pinfunction "PIO0_16/ADC0_4/FC4_TXD_SCL_MISO/CLKOUT/CT1_CAP0/R/R/EMC_CSN[0]/ENET_TXD0_27") (pintype "passive"))
    )
    (net (code "10") (name "/HV_ON") (class "Default")
      (node (ref "U3") (pin "41") (pinfunction "PIO1_10/ENET_TXD1/FC1_RXD_SDA_MOSI/CT1_MAT0/SCT0_OUT3/R/EMC_RASN_41") (pintype "passive"))
    )
    (net (code "11") (name "/ISP0") (class "Default")
      (node (ref "R6") (pin "2") (pinfunction "2_2") (pintype "passive"))
      (node (ref "U3") (pin "87") (pinfunction "PIO0_4/CAN0_RD/FC4_SCK/CT3_CAP0/SCT0_GPI4/R/EMC_D[2]/ENET_MDC_87") (pintype "passive"))
    )
    (net (code "12") (name "/ISP1") (class "Default")
      (node (ref "R5") (pin "2") (pinfunction "2_2") (pintype "passive"))
      (node (ref "U3") (pin "89") (pinfunction "PIO0_5/CAN0_TD/FC4_RXD_SDA_MOSI/CT3_MAT0/SCT0_GPI5/R/EMC_D[3]/ENET_MDIO_89") (pintype "passive"))
    )
    (net (code "13") (name "/ISP2") (class "Default")
      (node (ref "R4") (pin "2") (pinfunction "2_2") (pintype "passive"))
      (node (ref "U3") (pin "90") (pinfunction "PIO0_6/FC_SCK/CT3_CAP1/CT4_MAT0/SCT0_GPI6/R/EMC_D[4]/ENET_RX_DV_90") (pintype "passive"))
    )
    (net (code "14") (name "/ISP_RX_IN") (class "Default")
      (node (ref "U2") (pin "1") (pinfunction "RO_1") (pintype "passive"))
      (node (ref "U3") (pin "82") (pinfunction "PIO0_29/FC0_RXD_SDA_MOSI/R/CT2_MAT3/SCT0_OUT8/TRACEDATA[2]_82") (pintype "passive"))
    )
    (net (code "15") (name "/ISP_TX_OUT") (class "Default")
      (node (ref "U2") (pin "4") (pinfunction "DI_4") (pintype "passive"))
      (node (ref "U3") (pin "95") (pinfunction "PIO0_30/FC0_TXD_SCL_MISO/R/CT0_MAT0/SCT0_OUT9/TRACEDATA[1]_95") (pintype "passive"))
    )
    (net (code "16") (name "/MISC_FC_IO") (class "Default")
      (node (ref "U3") (pin "94") (pinfunction "PIO1_11/ENET_TX_EN/FC1_TXD_SCL_MISO/CT1_CAP1/USB0_VBUS/R/EMC_CLK[0]_94") (pintype "passive"))
    )
    (net (code "17") (name "/RS485_RX_IN_N") (class "Default")
      (node (ref "R1") (pin "1") (pinfunction "1_1") (pintype "passive"))
      (node (ref "U2") (pin "8") (pinfunction "B_8") (pintype "passive"))
    )
    (net (code "18") (name "/RS485_RX_IN_P") (class "Default")
      (node (ref "R1") (pin "2") (pinfunction "2_2") (pintype "passive"))
      (node (ref "U2") (pin "9") (pinfunction "A_9") (pintype "passive"))
    )
    (net (code "19") (name "/RS485_TX_OUT_N") (class "Default")
      (node (ref "U2") (pin "7") (pinfunction "Z_7") (pintype "passive"))
    )
    (net (code "20") (name "/RS485_TX_OUT_P") (class "Default")
      (node (ref "U2") (pin "6") (pinfunction "Y_6") (pintype "passive"))
    )
    (net (code "21") (name "/RST") (class "Default")
      (node (ref "J1") (pin "10") (pinfunction "~{RST}_10") (pintype "passive"))
      (node (ref "J2") (pin "3") (pinfunction "RST_3") (pintype "passive"))
      (node (ref "R8") (pin "1") (pinfunction "1_1") (pintype "passive"))
      (node (ref "U3") (pin "48") (pinfunction "RESETN_48") (pintype "passive"))
      (node (ref "U4") (pin "2") (pinfunction "~{RESET}_2") (pintype "passive"))
    )
    (net (code "22") (name "/RX_ENABLE") (class "Default")
      (node (ref "U2") (pin "2") (pinfunction "~{RE}_2") (pintype "passive"))
      (node (ref "U3") (pin "81") (pinfunction "PIO1_29/FC7_RXD_SDA_MOSI_DATA/SD_D[6]/SCT0_GPI6/USB1_PORTPWRN/USB1_FRAME/EMC_D[13]_81") (pintype "passive"))
    )
    (net (code "23") (name "/SCL") (class "Default")
      (node (ref "R2") (pin "1") (pinfunction "1_1") (pintype "passive"))
      (node (ref "U1") (pin "4") (pinfunction "SCL_4") (pintype "passive"))
      (node (ref "U3") (pin "83") (pinfunction "PIO0_2/FC3_TXD_SCL_MISO/CT0_CAP1/SCT0_OUT0/SCT0_GPI[2]/EMC_D[0]_83") (pintype "passive"))
    )
    (net (code "24") (name "/SDA") (class "Default")
      (node (ref "R3") (pin "1") (pinfunction "1_1") (pintype "passive"))
      (node (ref "U1") (pin "5") (pinfunction "SDA_5") (pintype "passive"))
      (node (ref "U3") (pin "85") (pinfunction "PIO0_3/FC3_RXD_SDA_MOSI/CT0_MAT1/SCT0_OUT1/SCT0_GPI3/R/EMC_D[1]_85") (pintype "passive"))
    )
    (net (code "25") (name "/SPIFI_CS") (class "Default")
      (node (ref "R9") (pin "1") (pinfunction "1_1") (pintype "passive"))
      (node (ref "U3") (pin "35") (pinfunction "PIO0_23/ADC0_11/MCLK/CT1_MAT2/CT3_MAT3/SCT0_OUT4/R/SPIFI_CSN_35") (pintype "passive"))
      (node (ref "U5") (pin "1") (pinfunction "~{CE}_1") (pintype "passive"))
    )
    (net (code "26") (name "/SPIFI_IO0") (class "Default")
      (node (ref "U3") (pin "38") (pinfunction "PIO0_24/FC0_RXD_SDA_MOSI/SD_D[0]/CT2_CAP0/SCT0_GPI0/R/SPIFI_IO0_38") (pintype "passive"))
      (node (ref "U3") (pin "40") (pinfunction "PIO0_25/FC0_TXD_SCL_MISO/SD_D[1]/CT2_CAP1/SCT0_GPI1/R/SPIFI_IO1_40") (pintype "passive"))
      (node (ref "U5") (pin "2") (pinfunction "SO_(IO1)_2") (pintype "passive"))
      (node (ref "U5") (pin "5") (pinfunction "SI_(IO0)_5") (pintype "passive"))
    )
    (net (code "27") (name "/SPIFI_IO2") (class "Default")
      (node (ref "U3") (pin "44") (pinfunction "PIO0_28/FC0_SCK/R/CT2_CAP3/SCT0_OUT7/TRACEDATA[3]/SPIFI_IO2/USB0_OVERCURRENTN_44") (pintype "passive"))
      (node (ref "U5") (pin "3") (pinfunction "~{WP}_(IO2)_3") (pintype "passive"))
    )
    (net (code "28") (name "/SPIFI_IO3") (class "Default")
      (node (ref "U3") (pin "42") (pinfunction "PIO0_27/FC2_TXD_SCL_MISO/R/CT3_MAT2/SCT0_OUT6/PDM0_DATA/SPIFI_IO3_42") (pintype "passive"))
      (node (ref "U5") (pin "7") (pinfunction "~{HOLD}_(IO3)_7") (pintype "passive"))
    )
    (net (code "29") (name "/SPIFI_SCK") (class "Default")
      (node (ref "U3") (pin "56") (pinfunction "PIO0_26/FC2_RXD_SDA_MOSI/CLKOUT/CT3_CAP2/SCT0_OUT5/PDM0_CLK/SPIFI_CLK/USB0_IDVALUE_56") (pintype "passive"))
      (node (ref "U5") (pin "6") (pinfunction "SCK_6") (pintype "passive"))
    )
    (net (code "30") (name "/SWDCLK") (class "Default")
      (node (ref "J1") (pin "4") (pinfunction "SWDCLK/TCK_4") (pintype "passive"))
      (node (ref "J2") (pin "4") (pinfunction "SWDCLK_4") (pintype "passive"))
      (node (ref "R16") (pin "1") (pinfunction "1_1") (pintype "passive"))
      (node (ref "U3") (pin "24") (pinfunction "PIO0_11/ADC0_1/FC6_RXD_SDA_MOSI_DATA/CT2_MAT2/FREQME_GPIO_CLK_A/R/R/SWCLK_24") (pintype "passive"))
    )
    (net (code "31") (name "/SWDIO") (class "Default")
      (node (ref "J1") (pin "2") (pinfunction "SWDIO/TMS_2") (pintype "passive"))
      (node (ref "J2") (pin "2") (pinfunction "SWDIO_2") (pintype "passive"))
      (node (ref "R17") (pin "1") (pinfunction "1_1") (pintype "passive"))
      (node (ref "U3") (pin "25") (pinfunction "PIO0_12/ADC0_2/FC3_TXD_SCL_MISO/R/FREQME_GPIO_CLK_B/SCT0_GPI7/R/SWDIO_25") (pintype "passive"))
    )
    (net (code "32") (name "/SWO") (class "Default")
      (node (ref "J1") (pin "6") (pinfunction "SWO/TDO_6") (pintype "passive"))
      (node (ref "J2") (pin "6") (pinfunction "SWO_6") (pintype "passive"))
      (node (ref "R15") (pin "1") (pinfunction "1_1") (pintype "passive"))
      (node (ref "U3") (pin "23") (pinfunction "PIO0_10/ADC0_0/FC6_SCK/CT2_CAP2/CT2_MAT0/FC1_TXD_SCL_MISO/R/SWO_23") (pintype "passive"))
    )
    (net (code "33") (name "/TDC1000_CLK") (class "Default")
      (node (ref "U1") (pin "10") (pinfunction "CLK0_10") (pintype "passive"))
    )
    (net (code "34") (name "/TDC7200_CLK") (class "Default")
      (node (ref "Y1") (pin "3") (pinfunction "OUTPUT_3") (pintype "passive"))
    )
    (net (code "35") (name "/TDC_ENABLE") (class "Default")
      (node (ref "U3") (pin "66") (pinfunction "PIO1_13/ENET_RXD1/FC6_RXD_SDA_MOSI_DATA/CT1_CAP2/USB0_OVERCURRENTN/USB0_FRAME/EMC_DQM[0]_66") (pintype "passive"))
    )
    (net (code "36") (name "/TDC_RESET") (class "Default")
      (node (ref "U3") (pin "63") (pinfunction "PIO1_26/FC2_CTS_SDA_SSEL0/SCT0_OUT3/CT0_CAP3/UTICK_CAP1/R/EMC_A[8]_63") (pintype "passive"))
    )
    (net (code "37") (name "/TDC_SPI_CLK") (class "Default")
      (node (ref "U3") (pin "16") (pinfunction "PIO1_19/FC8_SCK/SCT0_OUT7/CT3_MAT1/SCT0_GPI7/FC4_SCK/EMC_D[8]_16") (pintype "passive"))
    )
    (net (code "38") (name "/TDC_SPI_SDIN") (class "Default")
      (node (ref "U3") (pin "47") (pinfunction "PIO1_17/ENET_MDIO/FC8_RXD_SDA_MOSI/R/SCT0_OUT4/CAN1_TD/EMC_BLSN[0]_47") (pintype "passive"))
    )
    (net (code "39") (name "/TDC_SPI_SDO") (class "Default")
      (node (ref "U3") (pin "5") (pinfunction "PIO1_18/R/FC8_TXD_SCL_MISO/R/SCT0_OUT5/CAN1_RD/EMC_BLSN[1]_5") (pintype "passive"))
    )
    (net (code "40") (name "/TDC_START") (class "Default")
      (node (ref "U3") (pin "29") (pinfunction "PIO1_0/ACD0_6/FC0_RTS_SCL_SSEL1/SD_D[3]/CT0_CAP2/SCT0_GPI4/TRACECLK_29") (pintype "passive"))
    )
    (net (code "41") (name "/TDC_TRIGGER") (class "Default")
      (node (ref "U3") (pin "55") (pinfunction "PIO1_1/FC3_RXD_SDA_MOSI/R/CT0_CAP3/SCT0_GPI5/R/R/USB1_OVERCURRENTN_55") (pintype "passive"))
    )
    (net (code "42") (name "/TX_ENABLE") (class "Default")
      (node (ref "U2") (pin "3") (pinfunction "DE_3") (pintype "passive"))
      (node (ref "U3") (pin "73") (pinfunction "PIO1_28/FC7_SCK/SD_D[5]/CT0_CAP2/R/R/EMC_D[12]_73") (pintype "passive"))
    )
    (net (code "43") (name "/VIN_MONITOR") (class "Default")
      (node (ref "U3") (pin "26") (pinfunction "PIO0_15/ADC0_3/FC6_CTS_SDA_SSEL0/UTICK_CAP2/CT4_CAP0/SCT0_OUT2/R/EMC_WEN/ENET_TX_EN_26") (pintype "passive"))
    )
    (net (code "46") (name "GND") (class "Default")
      (node (ref "C1") (pin "1") (pinfunction "1_1") (pintype "passive"))
      (node (ref "C10") (pin "1") (pinfunction "1_1") (pintype "passive"))
      (node (ref "C11") (pin "1") (pinfunction "1_1") (pintype "passive"))
      (node (ref "C12") (pin "1") (pinfunction "1_1") (pintype "passive"))
      (node (ref "C13") (pin "1") (pinfunction "1_1") (pintype "passive"))
      (node (ref "C14") (pin "1") (pinfunction "1_1") (pintype "passive"))
      (node (ref "C15") (pin "1") (pinfunction "1_1") (pintype "passive"))
      (node (ref "C16") (pin "1") (pinfunction "1_1") (pintype "passive"))
      (node (ref "C17") (pin "1") (pinfunction "1_1") (pintype "passive"))
      (node (ref "C18") (pin "1") (pinfunction "1_1") (pintype "passive"))
      (node (ref "C19") (pin "1") (pinfunction "1_1") (pintype "passive"))
      (node (ref "C2") (pin "1") (pinfunction "1_1") (pintype "passive"))
      (node (ref "C20") (pin "1") (pinfunction "1_1") (pintype "passive"))
      (node (ref "C21") (pin "1") (pinfunction "1_1") (pintype "passive"))
      (node (ref "C3") (pin "1") (pinfunction "1_1") (pintype "passive"))
      (node (ref "C4") (pin "1") (pinfunction "1_1") (pintype "passive"))
      (node (ref "C5") (pin "1") (pinfunction "1_1") (pintype "passive"))
      (node (ref "C6") (pin "2") (pinfunction "1_2") (pintype "passive"))
      (node (ref "C7") (pin "1") (pinfunction "1_1") (pintype "passive"))
      (node (ref "C8") (pin "1") (pinfunction "1_1") (pintype "passive"))
      (node (ref "C9") (pin "1") (pinfunction "1_1") (pintype "passive"))
      (node (ref "D1") (pin "C") (pinfunction "C_C") (pintype "passive"))
      (node (ref "J1") (pin "3") (pinfunction "GND_3") (pintype "passive"))
      (node (ref "J1") (pin "5") (pinfunction "GND_5") (pintype "passive"))
      (node (ref "J1") (pin "9") (pinfunction "GND_DETECT_9") (pintype "passive"))
      (node (ref "J2") (pin "5") (pinfunction "GND_5") (pintype "passive"))
      (node (ref "R10") (pin "1") (pinfunction "1_1") (pintype "passive"))
      (node (ref "R11") (pin "1") (pinfunction "1_1") (pintype "passive"))
      (node (ref "R12") (pin "1") (pinfunction "1_1") (pintype "passive"))
      (node (ref "R13") (pin "1") (pinfunction "1_1") (pintype "passive"))
      (node (ref "R14") (pin "1") (pinfunction "1_1") (pintype "passive"))
      (node (ref "U1") (pin "8") (pinfunction "GND_8") (pintype "passive"))
      (node (ref "U2") (pin "5") (pinfunction "GND_5") (pintype "passive"))
      (node (ref "U3") (pin "14") (pinfunction "USB1_AVSSTX3V3_14") (pintype "passive"))
      (node (ref "U3") (pin "2") (pinfunction "VSS_2") (pintype "passive"))
      (node (ref "U3") (pin "22") (pinfunction "VSS_22") (pintype "passive"))
      (node (ref "U3") (pin "30") (pinfunction "VSSA_30") (pintype "passive"))
      (node (ref "U3") (pin "34") (pinfunction "VSS_34") (pintype "passive"))
      (node (ref "U3") (pin "43") (pinfunction "PIO1_22/FC8_RTS_SCL_SSEL1/SD_CMD/CT2_MAT3/SCT0_GPI5/FC4_SSEL3/EMC_CKE[1]_43") (pintype "passive"))
      (node (ref "U3") (pin "49") (pinfunction "VSS_49") (pintype "passive"))
      (node (ref "U3") (pin "51") (pinfunction "RTCXIN_51") (pintype "passive"))
      (node (ref "U3") (pin "53") (pinfunction "VSS_53") (pintype "passive"))
      (node (ref "U3") (pin "6") (pinfunction "USB1_AVSSC_6") (pintype "passive"))
      (node (ref "U3") (pin "71") (pinfunction "VSS_71") (pintype "passive"))
      (node (ref "U3") (pin "79") (pinfunction "VSS_79") (pintype "passive"))
      (node (ref "U3") (pin "80") (pinfunction "PIO0_22/FC6_TXD_SCL_MISO_WS/UTICK_CAP1/CT3_CAP3/SCT0_OUT3/R/R/USB0_VBUS_80") (pintype "passive"))
      (node (ref "U3") (pin "96") (pinfunction "VSS_96") (pintype "passive"))
      (node (ref "U4") (pin "1") (pinfunction "GND_1") (pintype "passive"))
      (node (ref "U5") (pin "4") (pinfunction "GND_4") (pintype "passive"))
      (node (ref "U6") (pin "2") (pinfunction "-_2") (pintype "passive"))
      (node (ref "Y1") (pin "2") (pinfunction "GND_2") (pintype "passive"))
    )
    (net (code "47") (name "Net-(D1-PadA)") (class "Default")
      (node (ref "D1") (pin "A") (pinfunction "A_A") (pintype "passive"))
      (node (ref "R7") (pin "1") (pinfunction "1_1") (pintype "passive"))
    )
    (net (code "48") (name "Net-(U1-CLK1)") (class "Default")
      (node (ref "TP1") (pin "1") (pinfunction "1_1") (pintype "passive"))
      (node (ref "U1") (pin "9") (pinfunction "CLK1_9") (pintype "passive"))
    )
    (net (code "49") (name "Net-(U1-XA)") (class "Default")
      (node (ref "C4") (pin "2") (pinfunction "1_2") (pintype "passive"))
      (node (ref "U1") (pin "2") (pinfunction "XA_2") (pintype "passive"))
      (node (ref "Y2") (pin "2") (pinfunction "OSC2_2") (pintype "passive"))
    )
    (net (code "50") (name "Net-(U1-XB)") (class "Default")
      (node (ref "C5") (pin "2") (pinfunction "1_2") (pintype "passive"))
      (node (ref "U1") (pin "3") (pinfunction "XB_3") (pintype "passive"))
      (node (ref "Y2") (pin "1") (pinfunction "OSC1_1") (pintype "passive"))
    )
    (net (code "51") (name "Net-(U3-PIO0_0{slash}CAN1_RD{slash}FC3_SCK{slash}Ctimer_MAT0{slash}SCT0_GPI0{slash}PDM0_CLK)") (class "Default")
      (node (ref "TP2") (pin "1") (pinfunction "1_1") (pintype "passive"))
      (node (ref "U3") (pin "93") (pinfunction "PIO0_0/CAN1_RD/FC3_SCK/Ctimer_MAT0/SCT0_GPI0/PDM0_CLK_93") (pintype "passive"))
    )
    (net (code "52") (name "Net-(U3-PIO0_1{slash}CAN1_TD{slash}FC3_CTS_SDA_SSEL0{slash}CT0_CAP0{slash}SCT0_GPI1{slash}PDM0_DATA)") (class "Default")
      (node (ref "TP3") (pin "1") (pinfunction "1_1") (pintype "passive"))
      (node (ref "U3") (pin "100") (pinfunction "PIO0_1/CAN1_TD/FC3_CTS_SDA_SSEL0/CT0_CAP0/SCT0_GPI1/PDM0_DATA_100") (pintype "passive"))
    )
    (net (code "53") (name "Net-(U3-PIO0_7{slash}FC3_RTS_SCL_SSEL1{slash}SD_CLK{slash}FC5_SCK{slash}FC1_SCK{slash}PDM1_CLK{slash}EMC_D[5]{slash}ENET_RX_CLK)") (class "Default")
      (node (ref "TP4") (pin "1") (pinfunction "1_1") (pintype "passive"))
      (node (ref "U3") (pin "61") (pinfunction "PIO0_7/FC3_RTS_SCL_SSEL1/SD_CLK/FC5_SCK/FC1_SCK/PDM1_CLK/EMC_D[5]/ENET_RX_CLK_61") (pintype "passive"))
    )
    (net (code "54") (name "Net-(U3-PIO0_8{slash}FC3_SSEL3{slash}SD_CMD{slash}FC5_RXD_SDA_MOSI{slash}SWO{slash}PDM1_DATA{slash}EMC_D[6])") (class "Default")
      (node (ref "TP5") (pin "1") (pinfunction "1_1") (pintype "passive"))
      (node (ref "U3") (pin "64") (pinfunction "PIO0_8/FC3_SSEL3/SD_CMD/FC5_RXD_SDA_MOSI/SWO/PDM1_DATA/EMC_D[6]_64") (pintype "passive"))
    )
    (net (code "55") (name "Net-(U3-PIO0_18{slash}FC4_CTS_SDA_SSEL0{slash}SD_WR_PRT{slash}CT1_MAT0{slash}SCT0_OUT1{slash}SCI1_SCLK{slash}EMC_A[0])") (class "Default")
      (node (ref "R7") (pin "2") (pinfunction "2_2") (pintype "passive"))
      (node (ref "U3") (pin "72") (pinfunction "PIO0_18/FC4_CTS_SDA_SSEL0/SD_WR_PRT/CT1_MAT0/SCT0_OUT1/SCI1_SCLK/EMC_A[0]_72") (pintype "passive"))
    )
    (net (code "56") (name "Net-(U3-PIO0_31{slash}ADC0_5{slash}FC0_CTS_SDA_SSEL0{slash}SD_D[2]{slash}CT0_MAT1{slash}SCT0_OUT3{slash}TRACEDATA[0])") (class "Default")
      (node (ref "TP6") (pin "1") (pinfunction "1_1") (pintype "passive"))
      (node (ref "U3") (pin "28") (pinfunction "PIO0_31/ADC0_5/FC0_CTS_SDA_SSEL0/SD_D[2]/CT0_MAT1/SCT0_OUT3/TRACEDATA[0]_28") (pintype "passive"))
    )
    (net (code "57") (name "Net-(U3-PIO1_21{slash}FC7_CTS_SDA_SSEL0{slash}R{slash}CT3_MAT2{slash}R{slash}FC4_RXD_SDA_MOSI{slash}EMC_D[10])") (class "Default")
      (node (ref "TP7") (pin "1") (pinfunction "1_1") (pintype "passive"))
      (node (ref "U3") (pin "37") (pinfunction "PIO1_21/FC7_CTS_SDA_SSEL0/R/CT3_MAT2/R/FC4_RXD_SDA_MOSI/EMC_D[10]_37") (pintype "passive"))
    )
    (net (code "58") (name "Net-(U3-PIO1_31{slash}MCLK{slash}R{slash}CT0_MAT2{slash}SCT0_OUT6{slash}FC8_CTS_SDA_SSEL0{slash}EMC_D[15])") (class "Default")
      (node (ref "TP8") (pin "1") (pinfunction "1_1") (pintype "passive"))
      (node (ref "U3") (pin "92") (pinfunction "PIO1_31/MCLK/R/CT0_MAT2/SCT0_OUT6/FC8_CTS_SDA_SSEL0/EMC_D[15]_92") (pintype "passive"))
    )
    (net (code "59") (name "Net-(U3-USB0_DM)") (class "Default")
      (node (ref "R10") (pin "2") (pinfunction "2_2") (pintype "passive"))
      (node (ref "U3") (pin "98") (pinfunction "USB0_DM_98") (pintype "passive"))
    )
    (net (code "60") (name "Net-(U3-USB0_DP)") (class "Default")
      (node (ref "R11") (pin "2") (pinfunction "2_2") (pintype "passive"))
      (node (ref "U3") (pin "97") (pinfunction "USB0_DP_97") (pintype "passive"))
    )
    (net (code "61") (name "Net-(U3-USB1_DM)") (class "Default")
      (node (ref "R12") (pin "2") (pinfunction "2_2") (pintype "passive"))
      (node (ref "U3") (pin "12") (pinfunction "USB1_DM_12") (pintype "passive"))
    )
    (net (code "62") (name "Net-(U3-USB1_DP)") (class "Default")
      (node (ref "R13") (pin "2") (pinfunction "2_2") (pintype "passive"))
      (node (ref "U3") (pin "13") (pinfunction "USB1_DP_13") (pintype "passive"))
    )
    (net (code "63") (name "Net-(U3-USB1_REXT)") (class "Default")
      (node (ref "R14") (pin "2") (pinfunction "2_2") (pintype "passive"))
      (node (ref "U3") (pin "7") (pinfunction "USB1_REXT_7") (pintype "passive"))
    )
    (net (code "64") (name "Net-(U3-XTALIN)") (class "Default")
      (node (ref "C15") (pin "2") (pinfunction "1_2") (pintype "passive"))
      (node (ref "U3") (pin "20") (pinfunction "XTALIN_20") (pintype "passive"))
      (node (ref "Y3") (pin "2") (pinfunction "OSC2_2") (pintype "passive"))
    )
    (net (code "65") (name "Net-(U3-XTALOUT)") (class "Default")
      (node (ref "C17") (pin "2") (pinfunction "1_2") (pintype "passive"))
      (node (ref "U3") (pin "19") (pinfunction "XTALOUT_19") (pintype "passive"))
      (node (ref "Y3") (pin "1") (pinfunction "OSC1_1") (pintype "passive"))
    )
    (net (code "66") (name "unconnected-(J1-KEY-Pad7)") (class "Default")
      (node (ref "J1") (pin "7") (pinfunction "KEY_7") (pintype "passive+no_connect"))
    )
    (net (code "67") (name "unconnected-(J1-TDI-Pad8)") (class "Default")
      (node (ref "J1") (pin "8") (pinfunction "TDI_8") (pintype "passive+no_connect"))
    )
    (net (code "68") (name "unconnected-(U3-PIO0_9{slash}FC3_SSEL2{slash}SD_POW_EN{slash}FC5_TXD_SCL_MISO{slash}R{slash}SCI1_IO{slash}EMC_D[7]-Pad65)") (class "Default")
      (node (ref "U3") (pin "65") (pinfunction "PIO0_9/FC3_SSEL2/SD_POW_EN/FC5_TXD_SCL_MISO/R/SCI1_IO/EMC_D[7]_65") (pintype "passive+no_connect"))
    )
    (net (code "69") (name "unconnected-(U3-PIO0_17{slash}FC4_SSEL2{slash}SD_CARD_DET_N{slash}SCT0_GPI7{slash}SCT0_OUT0{slash}R{slash}EMC_OEN{slash}ENET_TXD1-Pad70)") (class "Default")
      (node (ref "U3") (pin "70") (pinfunction "PIO0_17/FC4_SSEL2/SD_CARD_DET_N/SCT0_GPI7/SCT0_OUT0/R/EMC_OEN/ENET_TXD1_70") (pintype "passive"))
    )
    (net (code "70") (name "unconnected-(U3-PIO0_20{slash}FC3_CTS_SDA_SSEL0{slash}CT1_MAT1{slash}CT3_CAP3{slash}SCT0_GPI2{slash}SCI0_IO{slash}EMC_A[2]{slash}FC7_RXD_SDA_MOSI_DATA-Pad74)") (class "Default")
      (node (ref "U3") (pin "74") (pinfunction "PIO0_20/FC3_CTS_SDA_SSEL0/CT1_MAT1/CT3_CAP3/SCT0_GPI2/SCI0_IO/EMC_A[2]/FC7_RXD_SDA_MOSI_DATA_74") (pintype "passive+no_connect"))
    )
    (net (code "71") (name "unconnected-(U3-PIO0_21{slash}FC3_RTS_SCL_SSEL1{slash}UTICK_CAP3{slash}CT3_MAT3{slash}SCT0_GPI3{slash}SCI0_SCLK{slash}EMC_A[3]{slash}FC7_SCK-Pad77)") (class "Default")
      (node (ref "U3") (pin "77") (pinfunction "PIO0_21/FC3_RTS_SCL_SSEL1/UTICK_CAP3/CT3_MAT3/SCT0_GPI3/SCI0_SCLK/EMC_A[3]/FC7_SCK_77") (pintype "passive+no_connect"))
    )
    (net (code "72") (name "unconnected-(U3-PIO1_3{slash}CAN0_RD{slash}R{slash}R{slash}SCT0_OUT4{slash}PDM1_DATA{slash}USB0_PORTPWRN-Pad60)") (class "Default")
      (node (ref "U3") (pin "60") (pinfunction "PIO1_3/CAN0_RD/R/R/SCT0_OUT4/PDM1_DATA/USB0_PORTPWRN_60") (pintype "passive+no_connect"))
    )
    (net (code "73") (name "unconnected-(U3-PIO1_4{slash}FC0_SCK{slash}SD_D[0]{slash}CT2_MAT1{slash}SCT0_OUT0{slash}FREQMW_GPIO_CLK_A{slash}EMC_D[11]-Pad3)") (class "Default")
      (node (ref "U3") (pin "3") (pinfunction "PIO1_4/FC0_SCK/SD_D[0]/CT2_MAT1/SCT0_OUT0/FREQMW_GPIO_CLK_A/EMC_D[11]_3") (pintype "passive+no_connect"))
    )
    (net (code "74") (name "unconnected-(U3-PIO1_5{slash}FC0_RXD_SDA_MOSI{slash}SD_D[2]{slash}CT2_MAT0{slash}SCT0_GPI0{slash}R{slash}EMC_A[4]-Pad4)") (class "Default")
      (node (ref "U3") (pin "4") (pinfunction "PIO1_5/FC0_RXD_SDA_MOSI/SD_D[2]/CT2_MAT0/SCT0_GPI0/R/EMC_A[4]_4") (pintype "passive+no_connect"))
    )
    (net (code "75") (name "unconnected-(U3-PIO1_8{slash}FC0_CTS_SDA_SSEL0{slash}SD_CLK{slash}R{slash}SCT0_OUT1{slash}FC4_SSEL2{slash}EMC_A[7]-Pad36)") (class "Default")
      (node (ref "U3") (pin "36") (pinfunction "PIO1_8/FC0_CTS_SDA_SSEL0/SD_CLK/R/SCT0_OUT1/FC4_SSEL2/EMC_A[7]_36") (pintype "passive"))
    )
    (net (code "76") (name "unconnected-(U3-PIO1_12{slash}ENET_RXD0{slash}FC6_SCK{slash}CT1_MAT1{slash}USB0_PORTPWRN{slash}EMC_DYCSN[0]-Pad62)") (class "Default")
      (node (ref "U3") (pin "62") (pinfunction "PIO1_12/ENET_RXD0/FC6_SCK/CT1_MAT1/USB0_PORTPWRN/EMC_DYCSN[0]_62") (pintype "passive+no_connect"))
    )
    (net (code "77") (name "unconnected-(U3-PIO1_14{slash}ENET_RX_DV{slash}UTICK_CAP2{slash}CT1_MAT2{slash}FC5_CTS_SDA_SSEL0{slash}USB0_LEDN{slash}EMC_DQM[1]-Pad78)") (class "Default")
      (node (ref "U3") (pin "78") (pinfunction "PIO1_14/ENET_RX_DV/UTICK_CAP2/CT1_MAT2/FC5_CTS_SDA_SSEL0/USB0_LEDN/EMC_DQM[1]_78") (pintype "passive+no_connect"))
    )
    (net (code "78") (name "unconnected-(U3-PIO1_15{slash}ENET_RX_CLK{slash}UTICK_CAP3{slash}CT1_CAP3{slash}FC5_RTS_SCL_SSEL1{slash}FC4_RTS_SCL_SSEL1{slash}EMC_CKE[0]-Pad84)") (class "Default")
      (node (ref "U3") (pin "84") (pinfunction "PIO1_15/ENET_RX_CLK/UTICK_CAP3/CT1_CAP3/FC5_RTS_SCL_SSEL1/FC4_RTS_SCL_SSEL1/EMC_CKE[0]_84") (pintype "passive+no_connect"))
    )
    (net (code "79") (name "unconnected-(U3-PIO1_16{slash}ENET_MDC{slash}FC6_TXD_SCL_MISO_WS{slash}CT1_MAT3{slash}SD_CMD{slash}R{slash}EMC_A[10]-Pad88)") (class "Default")
      (node (ref "U3") (pin "88") (pinfunction "PIO1_16/ENET_MDC/FC6_TXD_SCL_MISO_WS/CT1_MAT3/SD_CMD/R/EMC_A[10]_88") (pintype "passive+no_connect"))
    )
    (net (code "80") (name "unconnected-(U3-PIO1_20{slash}FC7_RTS_SCL_SSEL1{slash}R{slash}CT3_CAP2{slash}R{slash}FC4_TXD_SCL_MISO{slash}EMC_D[9]-Pad17)") (class "Default")
      (node (ref "U3") (pin "17") (pinfunction "PIO1_20/FC7_RTS_SCL_SSEL1/R/CT3_CAP2/R/FC4_TXD_SCL_MISO/EMC_D[9]_17") (pintype "passive"))
    )
    (net (code "81") (name "unconnected-(U3-PIO1_23{slash}FC2_SCK{slash}SCT0_OUT0{slash}R{slash}ENET_MDIO{slash}FC3_SSEL2{slash}EMC_A[11]-Pad46)") (class "Default")
      (node (ref "U3") (pin "46") (pinfunction "PIO1_23/FC2_SCK/SCT0_OUT0/R/ENET_MDIO/FC3_SSEL2/EMC_A[11]_46") (pintype "passive+no_connect"))
    )
    (net (code "82") (name "unconnected-(U3-PIO1_24{slash}FC2_RXD_SDA_MOSI{slash}SCT0_OUT1{slash}R{slash}R{slash}FC3_SSEL3{slash}EMC_A[12]-Pad57)") (class "Default")
      (node (ref "U3") (pin "57") (pinfunction "PIO1_24/FC2_RXD_SDA_MOSI/SCT0_OUT1/R/R/FC3_SSEL3/EMC_A[12]_57") (pintype "passive+no_connect"))
    )
    (net (code "83") (name "unconnected-(U3-PIO1_25{slash}FC2_TXD_SCL_MISO{slash}SCT0_OUT2{slash}R{slash}UTICK_CAP0{slash}R{slash}EMC_A[13]-Pad59)") (class "Default")
      (node (ref "U3") (pin "59") (pinfunction "PIO1_25/FC2_TXD_SCL_MISO/SCT0_OUT2/R/UTICK_CAP0/R/EMC_A[13]_59") (pintype "passive+no_connect"))
    )
    (net (code "84") (name "unconnected-(U3-PIO1_27{slash}FC2_RTS_SCL_SSEL1{slash}SD_D[4]{slash}CT0_MAT3{slash}CLKOUT{slash}R{slash}EMC_A[9]-Pad68)") (class "Default")
      (node (ref "U3") (pin "68") (pinfunction "PIO1_27/FC2_RTS_SCL_SSEL1/SD_D[4]/CT0_MAT3/CLKOUT/R/EMC_A[9]_68") (pintype "passive+no_connect"))
    )
    (net (code "85") (name "unconnected-(U3-PIO1_30{slash}FC7_TXD_SCL_MISO_WS{slash}SD_D[7]{slash}SCT0_GPI7{slash}USB1_OVERCURRENTN{slash}USB1_LEDN{slash}EMC_D[14]-Pad86)") (class "Default")
      (node (ref "U3") (pin "86") (pinfunction "PIO1_30/FC7_TXD_SCL_MISO_WS/SD_D[7]/SCT0_GPI7/USB1_OVERCURRENTN/USB1_LEDN/EMC_D[14]_86") (pintype "passive+no_connect"))
    )
    (net (code "86") (name "unconnected-(U3-RTCXOUT-Pad52)") (class "Default")
      (node (ref "U3") (pin "52") (pinfunction "RTCXOUT_52") (pintype "passive+no_connect"))
    )
    (net (code "87") (name "unconnected-(U3-USB1_ID-Pad8)") (class "Default")
      (node (ref "U3") (pin "8") (pinfunction "USB1_ID_8") (pintype "passive+no_connect"))
    )
    (net (code "88") (name "unconnected-(U3-[OD]_PIO0_13{slash}FC1_CTS_SDA_SSEL0{slash}UTICK_CAP0{slash}CT0_CAP0{slash}SCT0_GPI0{slash}R{slash}R{slash}ENET_RXD0-Pad67)") (class "Default")
      (node (ref "U3") (pin "67") (pinfunction "[OD]_PIO0_13/FC1_CTS_SDA_SSEL0/UTICK_CAP0/CT0_CAP0/SCT0_GPI0/R/R/ENET_RXD0_67") (pintype "passive+no_connect"))
    )
    (net (code "89") (name "unconnected-(U3-[OD]_PIO0_14{slash}FC1_RTS_SCL_SSEL1{slash}UTICK_CAP1{slash}CT0_CAP1{slash}SCT0_GPI1{slash}R{slash}R{slash}ENET_RXD1-Pad69)") (class "Default")
      (node (ref "U3") (pin "69") (pinfunction "[OD]_PIO0_14/FC1_RTS_SCL_SSEL1/UTICK_CAP1/CT0_CAP1/SCT0_GPI1/R/R/ENET_RXD1_69") (pintype "passive+no_connect"))
    )
    (net (code "90") (name "unconnected-(Y1-NC-Pad1)") (class "Default")
      (node (ref "Y1") (pin "1") (pinfunction "NC_1") (pintype "passive+no_connect"))
    )
  )
)
